# 1-Schematic_spring_remote.net
KiCad netlist of a schematic drawn in EasyEDA
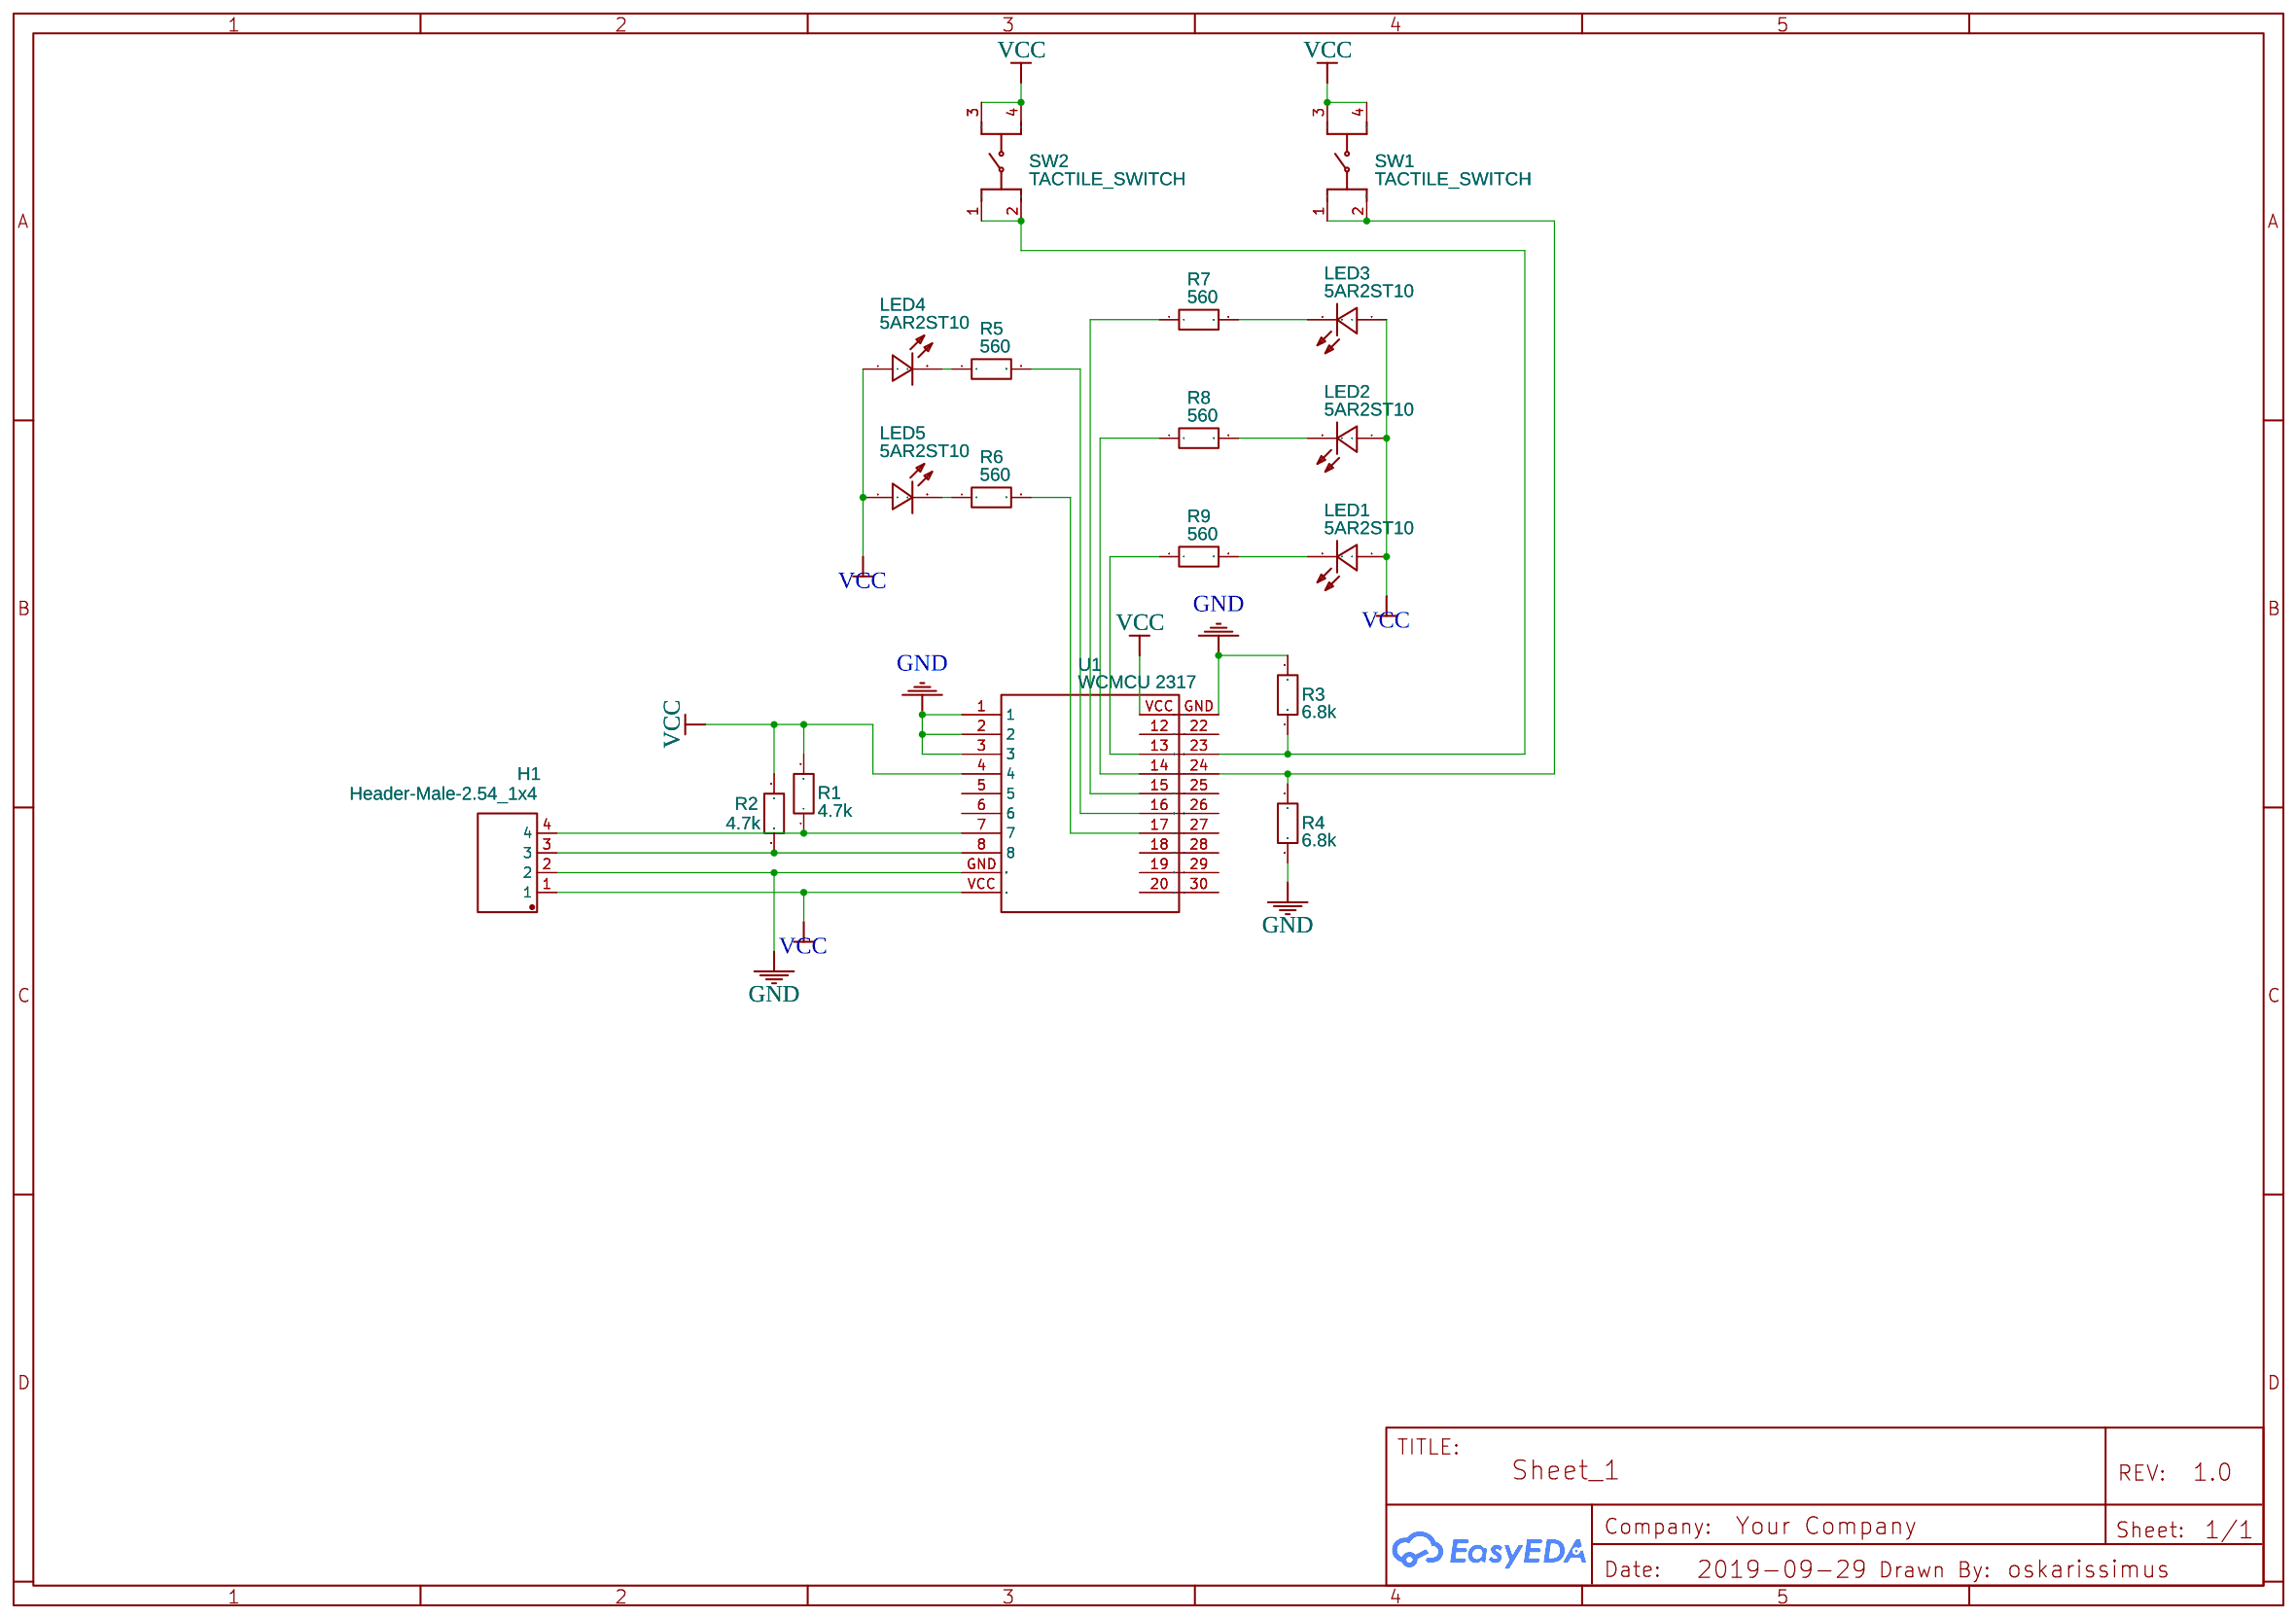
[diagram p0: schematic sheet]

(export (version "E")
  (design (tool "Eeschema 10.0.6"))
  (components
    (comp (ref "H1")
      (value "Header-Male-2.54_1x4")
      (fields
        (field (name "BOM_Manufacturer Part") "210S-1*4P L=11.6MMGold-plated black")
        (field (name "BOM_Supplier Part") "C124378")
      )
      (libsource (lib "") (part "Unknown_255_430"))
    )
    (comp (ref "LED1")
      (value "5AR2ST10")
      (fields (field (name "BOM_Supplier Part") "C52721"))
      (libsource (lib "") (part "Unknown_675_280"))
    )
    (comp (ref "LED2")
      (value "5AR2ST10")
      (fields (field (name "BOM_Supplier Part") "C52721"))
      (libsource (lib "") (part "Unknown_675_220"))
    )
    (comp (ref "LED3")
      (value "5AR2ST10")
      (fields (field (name "BOM_Supplier Part") "C52721"))
      (libsource (lib "") (part "Unknown_675_160"))
    )
    (comp (ref "LED4")
      (value "5AR2ST10")
      (fields (field (name "BOM_Supplier Part") "C52721"))
      (libsource (lib "") (part "Unknown_450_175"))
    )
    (comp (ref "LED5")
      (value "5AR2ST10")
      (fields (field (name "BOM_Supplier Part") "C52721"))
      (libsource (lib "") (part "Unknown_450_240"))
    )
    (comp (ref "R1") (value "4.7k") (libsource (lib "") (part "Res_AXIAL-0.3(1/8W)_EU_1")))
    (comp (ref "R2") (value "4.7k") (libsource (lib "") (part "Res_AXIAL-0.3(1/8W)_EU_2")))
    (comp (ref "R3") (value "6.8k") (libsource (lib "") (part "Res_AXIAL-0.3(1/8W)_EU_1")))
    (comp (ref "R4") (value "6.8k") (libsource (lib "") (part "Res_AXIAL-0.3(1/8W)_EU_1")))
    (comp (ref "R5") (value "560") (libsource (lib "") (part "Res_AXIAL-0.3(1/8W)_EU")))
    (comp (ref "R6") (value "560") (libsource (lib "") (part "Res_AXIAL-0.3(1/8W)_EU")))
    (comp (ref "R7") (value "560") (libsource (lib "") (part "Res_AXIAL-0.3(1/8W)_EU")))
    (comp (ref "R8") (value "560") (libsource (lib "") (part "Res_AXIAL-0.3(1/8W)_EU")))
    (comp (ref "R9") (value "560") (libsource (lib "") (part "Res_AXIAL-0.3(1/8W)_EU")))
    (comp (ref "SW1")
      (value "TACTILE_SWITCH")
      (fields
        (field (name "BOM_Manufacturer Part") "K2-6639SP-C4SC-04")
        (field (name "BOM_Supplier Part") "C83206")
      )
      (libsource (lib "") (part "Unknown_675_75"))
    )
    (comp (ref "SW2")
      (value "TACTILE_SWITCH")
      (fields
        (field (name "BOM_Manufacturer Part") "K2-6639SP-C4SC-04")
        (field (name "BOM_Supplier Part") "C83206")
      )
      (libsource (lib "") (part "Unknown_500_75"))
    )
    (comp (ref "U1") (value "WCMCU 2317") (libsource (lib "") (part "Unknown_510_355")))
  )
  (nets
    (net (code "1") (name "GND") (class "Default")
      (node (ref "H1") (pin "2") (pinfunction "2_2") (pintype "unspecified"))
      (node (ref "R3") (pin "2") (pinfunction "2_2") (pintype "unspecified"))
      (node (ref "R4") (pin "1") (pinfunction "1_1") (pintype "unspecified"))
      (node (ref "U1") (pin "1") (pinfunction "1_1") (pintype "unspecified"))
      (node (ref "U1") (pin "2") (pinfunction "2_2") (pintype "unspecified"))
      (node (ref "U1") (pin "3") (pinfunction "3_3") (pintype "unspecified"))
      (node (ref "U1") (pin "GND") (pinfunction "GND_GND") (pintype "passive"))
    )
    (net (code "2") (name "Net-(H1-Pad3)") (class "Default")
      (node (ref "H1") (pin "3") (pinfunction "3_3") (pintype "unspecified"))
      (node (ref "R2") (pin "2") (pinfunction "2_2") (pintype "unspecified"))
      (node (ref "U1") (pin "8") (pinfunction "8_8") (pintype "unspecified"))
    )
    (net (code "3") (name "Net-(H1-Pad4)") (class "Default")
      (node (ref "H1") (pin "4") (pinfunction "4_4") (pintype "unspecified"))
      (node (ref "R1") (pin "1") (pinfunction "1_1") (pintype "unspecified"))
      (node (ref "U1") (pin "7") (pinfunction "7_7") (pintype "unspecified"))
    )
    (net (code "4") (name "Net-(LED1-K)") (class "Default")
      (node (ref "LED1") (pin "2") (pinfunction "K_2") (pintype "unspecified"))
      (node (ref "R9") (pin "2") (pinfunction "2_2") (pintype "unspecified"))
    )
    (net (code "5") (name "Net-(LED2-K)") (class "Default")
      (node (ref "LED2") (pin "2") (pinfunction "K_2") (pintype "unspecified"))
      (node (ref "R8") (pin "2") (pinfunction "2_2") (pintype "unspecified"))
    )
    (net (code "6") (name "Net-(LED3-K)") (class "Default")
      (node (ref "LED3") (pin "2") (pinfunction "K_2") (pintype "unspecified"))
      (node (ref "R7") (pin "2") (pinfunction "2_2") (pintype "unspecified"))
    )
    (net (code "7") (name "Net-(LED4-K)") (class "Default")
      (node (ref "LED4") (pin "2") (pinfunction "K_2") (pintype "unspecified"))
      (node (ref "R5") (pin "1") (pinfunction "1_1") (pintype "unspecified"))
    )
    (net (code "8") (name "Net-(LED5-K)") (class "Default")
      (node (ref "LED5") (pin "2") (pinfunction "K_2") (pintype "unspecified"))
      (node (ref "R6") (pin "1") (pinfunction "1_1") (pintype "unspecified"))
    )
    (net (code "9") (name "Net-(R3-Pad1)") (class "Default")
      (node (ref "R3") (pin "1") (pinfunction "1_1") (pintype "unspecified"))
      (node (ref "SW2") (pin "1") (pinfunction "1_1") (pintype "unspecified"))
      (node (ref "SW2") (pin "2") (pinfunction "2_2") (pintype "unspecified"))
      (node (ref "U1") (pin "23") (pinfunction "23_23") (pintype "unspecified"))
    )
    (net (code "10") (name "Net-(R4-Pad2)") (class "Default")
      (node (ref "R4") (pin "2") (pinfunction "2_2") (pintype "unspecified"))
      (node (ref "SW1") (pin "1") (pinfunction "1_1") (pintype "unspecified"))
      (node (ref "SW1") (pin "2") (pinfunction "2_2") (pintype "unspecified"))
      (node (ref "U1") (pin "24") (pinfunction "24_24") (pintype "unspecified"))
    )
    (net (code "11") (name "Net-(R5-Pad2)") (class "Default")
      (node (ref "R5") (pin "2") (pinfunction "2_2") (pintype "unspecified"))
      (node (ref "U1") (pin "16") (pinfunction "16_16") (pintype "unspecified"))
    )
    (net (code "12") (name "Net-(R6-Pad2)") (class "Default")
      (node (ref "R6") (pin "2") (pinfunction "2_2") (pintype "unspecified"))
      (node (ref "U1") (pin "17") (pinfunction "17_17") (pintype "unspecified"))
    )
    (net (code "13") (name "Net-(R7-Pad1)") (class "Default")
      (node (ref "R7") (pin "1") (pinfunction "1_1") (pintype "unspecified"))
      (node (ref "U1") (pin "15") (pinfunction "15_15") (pintype "unspecified"))
    )
    (net (code "14") (name "Net-(R8-Pad1)") (class "Default")
      (node (ref "R8") (pin "1") (pinfunction "1_1") (pintype "unspecified"))
      (node (ref "U1") (pin "14") (pinfunction "14_14") (pintype "unspecified"))
    )
    (net (code "15") (name "Net-(R9-Pad1)") (class "Default")
      (node (ref "R9") (pin "1") (pinfunction "1_1") (pintype "unspecified"))
      (node (ref "U1") (pin "13") (pinfunction "13_13") (pintype "unspecified"))
    )
    (net (code "16") (name "VCC") (class "Default")
      (node (ref "H1") (pin "1") (pinfunction "1_1") (pintype "unspecified"))
      (node (ref "LED1") (pin "1") (pinfunction "A_1") (pintype "unspecified"))
      (node (ref "LED2") (pin "1") (pinfunction "A_1") (pintype "unspecified"))
      (node (ref "LED3") (pin "1") (pinfunction "A_1") (pintype "unspecified"))
      (node (ref "LED4") (pin "1") (pinfunction "A_1") (pintype "unspecified"))
      (node (ref "LED5") (pin "1") (pinfunction "A_1") (pintype "unspecified"))
      (node (ref "R1") (pin "2") (pinfunction "2_2") (pintype "unspecified"))
      (node (ref "R2") (pin "1") (pinfunction "1_1") (pintype "unspecified"))
      (node (ref "SW1") (pin "3") (pinfunction "3_3") (pintype "unspecified"))
      (node (ref "SW1") (pin "4") (pinfunction "4_4") (pintype "unspecified"))
      (node (ref "SW2") (pin "3") (pinfunction "3_3") (pintype "unspecified"))
      (node (ref "SW2") (pin "4") (pinfunction "4_4") (pintype "unspecified"))
      (node (ref "U1") (pin "4") (pinfunction "4_4") (pintype "unspecified"))
      (node (ref "U1") (pin "VCC") (pinfunction "VCC_VCC") (pintype "passive"))
    )
    (net (code "17") (name "unconnected-(U1-Pad5)") (class "Default")
      (node (ref "U1") (pin "5") (pinfunction "5_5") (pintype "unspecified"))
    )
    (net (code "18") (name "unconnected-(U1-Pad6)") (class "Default")
      (node (ref "U1") (pin "6") (pinfunction "6_6") (pintype "unspecified"))
    )
    (net (code "19") (name "unconnected-(U1-Pad12)") (class "Default")
      (node (ref "U1") (pin "12") (pinfunction "12_12") (pintype "unspecified"))
    )
    (net (code "20") (name "unconnected-(U1-Pad18)") (class "Default")
      (node (ref "U1") (pin "18") (pinfunction "18_18") (pintype "unspecified"))
    )
    (net (code "21") (name "unconnected-(U1-Pad19)") (class "Default")
      (node (ref "U1") (pin "19") (pinfunction "19_19") (pintype "unspecified"))
    )
    (net (code "22") (name "unconnected-(U1-Pad20)") (class "Default")
      (node (ref "U1") (pin "20") (pinfunction "20_20") (pintype "unspecified"))
    )
    (net (code "23") (name "unconnected-(U1-Pad22)") (class "Default")
      (node (ref "U1") (pin "22") (pinfunction "22_22") (pintype "unspecified"))
    )
    (net (code "24") (name "unconnected-(U1-Pad25)") (class "Default")
      (node (ref "U1") (pin "25") (pinfunction "25_25") (pintype "unspecified"))
    )
    (net (code "25") (name "unconnected-(U1-Pad26)") (class "Default")
      (node (ref "U1") (pin "26") (pinfunction "26_26") (pintype "unspecified"))
    )
    (net (code "26") (name "unconnected-(U1-Pad27)") (class "Default")
      (node (ref "U1") (pin "27") (pinfunction "27_27") (pintype "unspecified"))
    )
    (net (code "27") (name "unconnected-(U1-Pad28)") (class "Default")
      (node (ref "U1") (pin "28") (pinfunction "28_28") (pintype "unspecified"))
    )
    (net (code "28") (name "unconnected-(U1-Pad29)") (class "Default")
      (node (ref "U1") (pin "29") (pinfunction "29_29") (pintype "unspecified"))
    )
    (net (code "29") (name "unconnected-(U1-Pad30)") (class "Default")
      (node (ref "U1") (pin "30") (pinfunction "30_30") (pintype "unspecified"))
    )
  )
)
